# UniConnector.net
KiCad netlist of a schematic drawn in Altium Designer
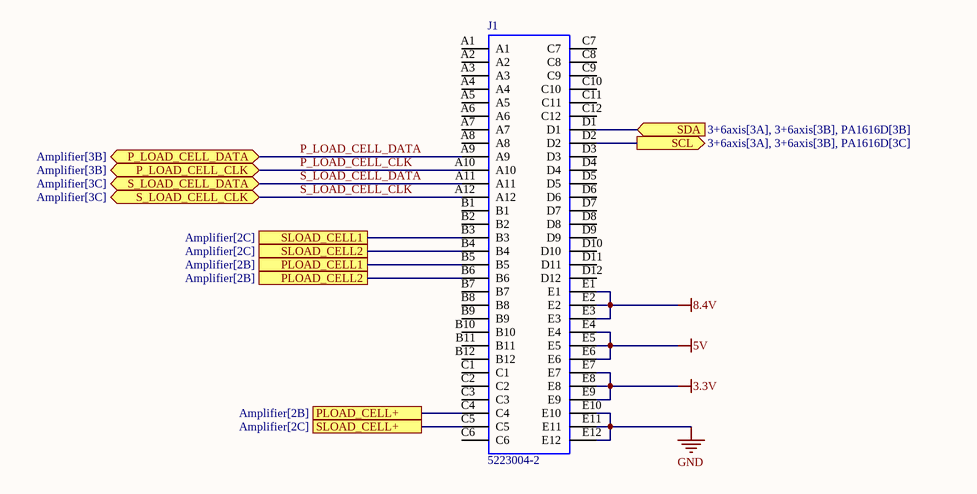
[diagram p0: UniConnector.SchDoc]

(export (version "E")
  (design (tool "Eeschema 10.0.6"))
  (components
    (comp (ref "J1")
      (value "5223004-2")
      (footprint "52230042")
      (description "Conn Backplane RCP 60 POS 2mm Solder RA Thru-Hole Tube")
      (fields (field (name "MOUSER PART NUMBER") "571-5223004-2"))
      (libsource (lib "5223004-2") (part "5223004-2"))
    )
  )
  (nets
    (net (code "1") (name "/PLOAD_CELL+") (class "Default")
      (node (ref "J1") (pin "C4") (pinfunction "C4_C4") (pintype "passive"))
    )
    (net (code "2") (name "/PLOAD_CELL1") (class "Default")
      (node (ref "J1") (pin "B5") (pinfunction "B5_B5") (pintype "passive"))
    )
    (net (code "3") (name "/PLOAD_CELL2") (class "Default")
      (node (ref "J1") (pin "B6") (pinfunction "B6_B6") (pintype "passive"))
    )
    (net (code "4") (name "/P_LOAD_CELL_CLK") (class "Default")
      (node (ref "J1") (pin "A10") (pinfunction "A10_A10") (pintype "passive"))
    )
    (net (code "5") (name "/P_LOAD_CELL_DATA") (class "Default")
      (node (ref "J1") (pin "A9") (pinfunction "A9_A9") (pintype "passive"))
    )
    (net (code "6") (name "/SCL") (class "Default")
      (node (ref "J1") (pin "D2") (pinfunction "D2_D2") (pintype "passive"))
    )
    (net (code "7") (name "/SDA") (class "Default")
      (node (ref "J1") (pin "D1") (pinfunction "D1_D1") (pintype "passive"))
    )
    (net (code "8") (name "/SLOAD_CELL+") (class "Default")
      (node (ref "J1") (pin "C5") (pinfunction "C5_C5") (pintype "passive"))
    )
    (net (code "9") (name "/SLOAD_CELL1") (class "Default")
      (node (ref "J1") (pin "B3") (pinfunction "B3_B3") (pintype "passive"))
    )
    (net (code "10") (name "/SLOAD_CELL2") (class "Default")
      (node (ref "J1") (pin "B4") (pinfunction "B4_B4") (pintype "passive"))
    )
    (net (code "11") (name "/S_LOAD_CELL_CLK") (class "Default")
      (node (ref "J1") (pin "A12") (pinfunction "A12_A12") (pintype "passive"))
    )
    (net (code "12") (name "/S_LOAD_CELL_DATA") (class "Default")
      (node (ref "J1") (pin "A11") (pinfunction "A11_A11") (pintype "passive"))
    )
    (net (code "13") (name "3.3V") (class "Default")
      (node (ref "J1") (pin "E7") (pinfunction "E7_E7") (pintype "passive"))
      (node (ref "J1") (pin "E8") (pinfunction "E8_E8") (pintype "passive"))
      (node (ref "J1") (pin "E9") (pinfunction "E9_E9") (pintype "passive"))
    )
    (net (code "14") (name "5V") (class "Default")
      (node (ref "J1") (pin "E4") (pinfunction "E4_E4") (pintype "passive"))
      (node (ref "J1") (pin "E5") (pinfunction "E5_E5") (pintype "passive"))
      (node (ref "J1") (pin "E6") (pinfunction "E6_E6") (pintype "passive"))
    )
    (net (code "15") (name "8.4V") (class "Default")
      (node (ref "J1") (pin "E1") (pinfunction "E1_E1") (pintype "passive"))
      (node (ref "J1") (pin "E2") (pinfunction "E2_E2") (pintype "passive"))
      (node (ref "J1") (pin "E3") (pinfunction "E3_E3") (pintype "passive"))
    )
    (net (code "16") (name "GND") (class "Default")
      (node (ref "J1") (pin "E10") (pinfunction "E10_E10") (pintype "passive"))
      (node (ref "J1") (pin "E11") (pinfunction "E11_E11") (pintype "passive"))
      (node (ref "J1") (pin "E12") (pinfunction "E12_E12") (pintype "passive"))
    )
    (net (code "17") (name "unconnected-(J1-PadA1)") (class "Default")
      (node (ref "J1") (pin "A1") (pinfunction "A1_A1") (pintype "passive"))
    )
    (net (code "18") (name "unconnected-(J1-PadA2)") (class "Default")
      (node (ref "J1") (pin "A2") (pinfunction "A2_A2") (pintype "passive"))
    )
    (net (code "19") (name "unconnected-(J1-PadA3)") (class "Default")
      (node (ref "J1") (pin "A3") (pinfunction "A3_A3") (pintype "passive"))
    )
    (net (code "20") (name "unconnected-(J1-PadA4)") (class "Default")
      (node (ref "J1") (pin "A4") (pinfunction "A4_A4") (pintype "passive"))
    )
    (net (code "21") (name "unconnected-(J1-PadA5)") (class "Default")
      (node (ref "J1") (pin "A5") (pinfunction "A5_A5") (pintype "passive"))
    )
    (net (code "22") (name "unconnected-(J1-PadA6)") (class "Default")
      (node (ref "J1") (pin "A6") (pinfunction "A6_A6") (pintype "passive"))
    )
    (net (code "23") (name "unconnected-(J1-PadA7)") (class "Default")
      (node (ref "J1") (pin "A7") (pinfunction "A7_A7") (pintype "passive"))
    )
    (net (code "24") (name "unconnected-(J1-PadA8)") (class "Default")
      (node (ref "J1") (pin "A8") (pinfunction "A8_A8") (pintype "passive"))
    )
    (net (code "25") (name "unconnected-(J1-PadB1)") (class "Default")
      (node (ref "J1") (pin "B1") (pinfunction "B1_B1") (pintype "passive"))
    )
    (net (code "26") (name "unconnected-(J1-PadB2)") (class "Default")
      (node (ref "J1") (pin "B2") (pinfunction "B2_B2") (pintype "passive"))
    )
    (net (code "27") (name "unconnected-(J1-PadB7)") (class "Default")
      (node (ref "J1") (pin "B7") (pinfunction "B7_B7") (pintype "passive"))
    )
    (net (code "28") (name "unconnected-(J1-PadB8)") (class "Default")
      (node (ref "J1") (pin "B8") (pinfunction "B8_B8") (pintype "passive"))
    )
    (net (code "29") (name "unconnected-(J1-PadB9)") (class "Default")
      (node (ref "J1") (pin "B9") (pinfunction "B9_B9") (pintype "passive"))
    )
    (net (code "30") (name "unconnected-(J1-PadB10)") (class "Default")
      (node (ref "J1") (pin "B10") (pinfunction "B10_B10") (pintype "passive"))
    )
    (net (code "31") (name "unconnected-(J1-PadB11)") (class "Default")
      (node (ref "J1") (pin "B11") (pinfunction "B11_B11") (pintype "passive"))
    )
    (net (code "32") (name "unconnected-(J1-PadB12)") (class "Default")
      (node (ref "J1") (pin "B12") (pinfunction "B12_B12") (pintype "passive"))
    )
    (net (code "33") (name "unconnected-(J1-PadC1)") (class "Default")
      (node (ref "J1") (pin "C1") (pinfunction "C1_C1") (pintype "passive"))
    )
    (net (code "34") (name "unconnected-(J1-PadC2)") (class "Default")
      (node (ref "J1") (pin "C2") (pinfunction "C2_C2") (pintype "passive"))
    )
    (net (code "35") (name "unconnected-(J1-PadC3)") (class "Default")
      (node (ref "J1") (pin "C3") (pinfunction "C3_C3") (pintype "passive"))
    )
    (net (code "36") (name "unconnected-(J1-PadC6)") (class "Default")
      (node (ref "J1") (pin "C6") (pinfunction "C6_C6") (pintype "passive"))
    )
    (net (code "37") (name "unconnected-(J1-PadC7)") (class "Default")
      (node (ref "J1") (pin "C7") (pinfunction "C7_C7") (pintype "passive"))
    )
    (net (code "38") (name "unconnected-(J1-PadC8)") (class "Default")
      (node (ref "J1") (pin "C8") (pinfunction "C8_C8") (pintype "passive"))
    )
    (net (code "39") (name "unconnected-(J1-PadC9)") (class "Default")
      (node (ref "J1") (pin "C9") (pinfunction "C9_C9") (pintype "passive"))
    )
    (net (code "40") (name "unconnected-(J1-PadC10)") (class "Default")
      (node (ref "J1") (pin "C10") (pinfunction "C10_C10") (pintype "passive"))
    )
    (net (code "41") (name "unconnected-(J1-PadC11)") (class "Default")
      (node (ref "J1") (pin "C11") (pinfunction "C11_C11") (pintype "passive"))
    )
    (net (code "42") (name "unconnected-(J1-PadC12)") (class "Default")
      (node (ref "J1") (pin "C12") (pinfunction "C12_C12") (pintype "passive"))
    )
    (net (code "43") (name "unconnected-(J1-PadD3)") (class "Default")
      (node (ref "J1") (pin "D3") (pinfunction "D3_D3") (pintype "passive"))
    )
    (net (code "44") (name "unconnected-(J1-PadD4)") (class "Default")
      (node (ref "J1") (pin "D4") (pinfunction "D4_D4") (pintype "passive"))
    )
    (net (code "45") (name "unconnected-(J1-PadD5)") (class "Default")
      (node (ref "J1") (pin "D5") (pinfunction "D5_D5") (pintype "passive"))
    )
    (net (code "46") (name "unconnected-(J1-PadD6)") (class "Default")
      (node (ref "J1") (pin "D6") (pinfunction "D6_D6") (pintype "passive"))
    )
    (net (code "47") (name "unconnected-(J1-PadD7)") (class "Default")
      (node (ref "J1") (pin "D7") (pinfunction "D7_D7") (pintype "passive"))
    )
    (net (code "48") (name "unconnected-(J1-PadD8)") (class "Default")
      (node (ref "J1") (pin "D8") (pinfunction "D8_D8") (pintype "passive"))
    )
    (net (code "49") (name "unconnected-(J1-PadD9)") (class "Default")
      (node (ref "J1") (pin "D9") (pinfunction "D9_D9") (pintype "passive"))
    )
    (net (code "50") (name "unconnected-(J1-PadD10)") (class "Default")
      (node (ref "J1") (pin "D10") (pinfunction "D10_D10") (pintype "passive"))
    )
    (net (code "51") (name "unconnected-(J1-PadD11)") (class "Default")
      (node (ref "J1") (pin "D11") (pinfunction "D11_D11") (pintype "passive"))
    )
    (net (code "52") (name "unconnected-(J1-PadD12)") (class "Default")
      (node (ref "J1") (pin "D12") (pinfunction "D12_D12") (pintype "passive"))
    )
  )
)
